# ADC.net
KiCad netlist of a schematic drawn in Altium Designer
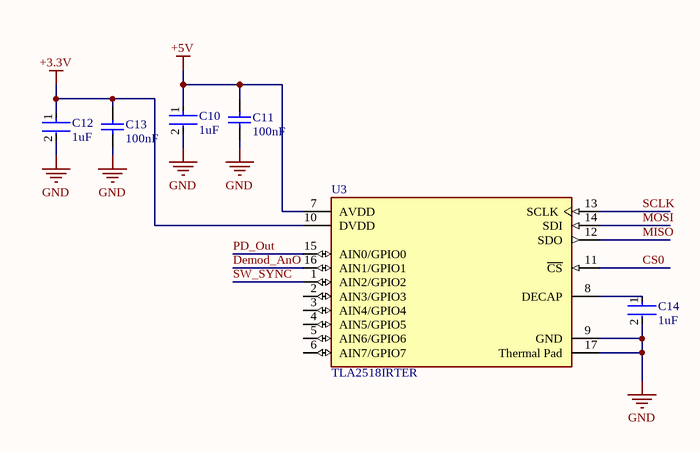
[diagram p0: ADC.SchDoc]

(export (version "E")
  (design (tool "Eeschema 10.0.6"))
  (components
    (comp (ref "C10")
      (value "1uF")
      (footprint "FP-CL542-IPC_C")
      (description "Cap Ceramic 1uF 25V X5R ±10% SMD 0402 +85°C Paper T/R")
      (fields (field (name "TOLERANCE") "10%"))
      (libsource (lib "Altium Content Vault") (part "b4654b650e69147ec39a6b967a45e02"))
    )
    (comp (ref "C11")
      (value "100nF")
      (footprint "CAPC1050X55X23ML05T13")
      (description "Chip Capacitor, 100 nF, +/- 10%, 16 V, -55 to 125 degC, 0402 (1005 Metric), RoHS, Tape and Reel")
      (fields (field (name "MANUFACTURER") "Samsung Electro-Mechanics"))
      (libsource (lib "Altium Content Vault") (part "CAP-NP-2"))
    )
    (comp (ref "C12")
      (value "1uF")
      (footprint "FP-CL542-IPC_C")
      (description "Cap Ceramic 1uF 25V X5R ±10% SMD 0402 +85°C Paper T/R")
      (fields (field (name "TOLERANCE") "10%"))
      (libsource (lib "Altium Content Vault") (part "b4654b650e69147ec39a6b967a45e02"))
    )
    (comp (ref "C13")
      (value "100nF")
      (footprint "CAPC1050X55X23ML05T13")
      (description "Chip Capacitor, 100 nF, +/- 10%, 16 V, -55 to 125 degC, 0402 (1005 Metric), RoHS, Tape and Reel")
      (fields (field (name "MANUFACTURER") "Samsung Electro-Mechanics"))
      (libsource (lib "Altium Content Vault") (part "CAP-NP-2"))
    )
    (comp (ref "C14")
      (value "1uF")
      (footprint "FP-CL542-IPC_C")
      (description "Cap Ceramic 1uF 25V X5R ±10% SMD 0402 +85°C Paper T/R")
      (fields (field (name "TOLERANCE") "10%"))
      (libsource (lib "Altium Content Vault") (part "b4654b650e69147ec39a6b967a45e02"))
    )
    (comp (ref "U3")
      (value "TLA2518IRTER")
      (footprint "FP-RTE0016C-MFG")
      (description "IC ADC 12BIT SAR 16WQFN")
      (libsource (lib "Altium Content Vault") (part "ea188d9e188d8d00ef3d327048906ac"))
    )
  )
  (nets
    (net (code "1") (name "+3.3V") (class "Default")
      (node (ref "C12") (pin "1") (pinfunction "1_1") (pintype "passive"))
      (node (ref "C13") (pin "2") (pinfunction "2_2") (pintype "passive"))
      (node (ref "U3") (pin "10") (pinfunction "DVDD_10") (pintype "power_in"))
    )
    (net (code "2") (name "+5V") (class "Default")
      (node (ref "C10") (pin "1") (pinfunction "1_1") (pintype "passive"))
      (node (ref "C11") (pin "2") (pinfunction "2_2") (pintype "passive"))
      (node (ref "U3") (pin "7") (pinfunction "AVDD_7") (pintype "power_in"))
    )
    (net (code "3") (name "/CS0") (class "Default")
      (node (ref "U3") (pin "11") (pinfunction "~{CS}_11") (pintype "input"))
    )
    (net (code "4") (name "/Demod_AnO") (class "Default")
      (node (ref "U3") (pin "16") (pinfunction "AIN1/GPIO1_16") (pintype "bidirectional"))
    )
    (net (code "5") (name "/MISO") (class "Default")
      (node (ref "U3") (pin "12") (pinfunction "SDO_12") (pintype "output"))
    )
    (net (code "6") (name "/MOSI") (class "Default")
      (node (ref "U3") (pin "14") (pinfunction "SDI_14") (pintype "input"))
    )
    (net (code "7") (name "/PD_Out") (class "Default")
      (node (ref "U3") (pin "15") (pinfunction "AIN0/GPIO0_15") (pintype "bidirectional"))
    )
    (net (code "8") (name "/SCLK") (class "Default")
      (node (ref "U3") (pin "13") (pinfunction "SCLK_13") (pintype "input"))
    )
    (net (code "9") (name "/SW_SYNC") (class "Default")
      (node (ref "U3") (pin "1") (pinfunction "AIN2/GPIO2_1") (pintype "bidirectional"))
    )
    (net (code "10") (name "GND") (class "Default")
      (node (ref "C10") (pin "2") (pinfunction "2_2") (pintype "passive"))
      (node (ref "C11") (pin "1") (pinfunction "1_1") (pintype "passive"))
      (node (ref "C12") (pin "2") (pinfunction "2_2") (pintype "passive"))
      (node (ref "C13") (pin "1") (pinfunction "1_1") (pintype "passive"))
      (node (ref "C14") (pin "2") (pinfunction "2_2") (pintype "passive"))
      (node (ref "U3") (pin "17") (pinfunction "Thermal_Pad_17") (pintype "power_in"))
      (node (ref "U3") (pin "9") (pinfunction "GND_9") (pintype "power_in"))
    )
    (net (code "11") (name "Net-(U3-DECAP)") (class "Default")
      (node (ref "C14") (pin "1") (pinfunction "1_1") (pintype "passive"))
      (node (ref "U3") (pin "8") (pinfunction "DECAP_8") (pintype "passive"))
    )
    (net (code "12") (name "unconnected-(U3-AIN3{slash}GPIO3-Pad2)") (class "Default")
      (node (ref "U3") (pin "2") (pinfunction "AIN3/GPIO3_2") (pintype "bidirectional"))
    )
    (net (code "13") (name "unconnected-(U3-AIN4{slash}GPIO4-Pad3)") (class "Default")
      (node (ref "U3") (pin "3") (pinfunction "AIN4/GPIO4_3") (pintype "bidirectional"))
    )
    (net (code "14") (name "unconnected-(U3-AIN5{slash}GPIO5-Pad4)") (class "Default")
      (node (ref "U3") (pin "4") (pinfunction "AIN5/GPIO5_4") (pintype "bidirectional"))
    )
    (net (code "15") (name "unconnected-(U3-AIN6{slash}GPIO6-Pad5)") (class "Default")
      (node (ref "U3") (pin "5") (pinfunction "AIN6/GPIO6_5") (pintype "bidirectional"))
    )
    (net (code "16") (name "unconnected-(U3-AIN7{slash}GPIO7-Pad6)") (class "Default")
      (node (ref "U3") (pin "6") (pinfunction "AIN7/GPIO7_6") (pintype "bidirectional"))
    )
  )
)
